# serial-con.net
KiCad netlist of a schematic drawn in Altium Designer
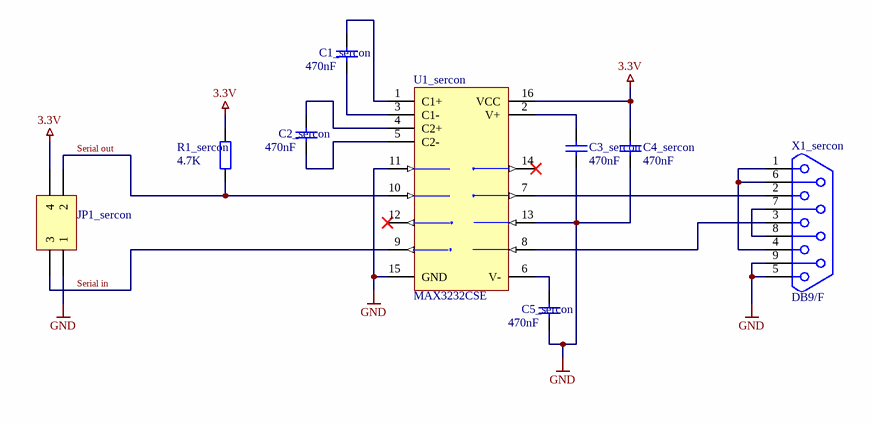
[diagram p0: serial-con.SchDoc]

(export (version "E")
  (design (tool "Eeschema 10.0.6"))
  (components
    (comp (ref "1_sercon")
      (value "CC License")
      (footprint "CC-License")
      (libsource (lib "gecko3-user") (part "CC License"))
    )
    (comp (ref "C1_sercon")
      (value "470nF")
      (footprint "0603")
      (description "Capacitor")
      (fields
        (field (name "MANUFACTURER") "PHYCOMP")
        (field (name "PART NUMBER") "2238 786 19758")
        (field (name "PUBLISHER") "Altium Limited")
      )
      (libsource (lib "Miscellaneous Devices") (part "Cap"))
    )
    (comp (ref "C2_sercon")
      (value "470nF")
      (footprint "0603")
      (description "Capacitor")
      (fields
        (field (name "MANUFACTURER") "PHYCOMP")
        (field (name "PART NUMBER") "2238 786 19758")
        (field (name "PUBLISHER") "Altium Limited")
      )
      (libsource (lib "Miscellaneous Devices") (part "Cap"))
    )
    (comp (ref "C3_sercon")
      (value "470nF")
      (footprint "0603")
      (description "Capacitor")
      (fields
        (field (name "MANUFACTURER") "PHYCOMP")
        (field (name "PART NUMBER") "2238 786 19758")
        (field (name "PUBLISHER") "Altium Limited")
      )
      (libsource (lib "Miscellaneous Devices") (part "Cap"))
    )
    (comp (ref "C4_sercon")
      (value "470nF")
      (footprint "0603")
      (description "Capacitor")
      (fields
        (field (name "MANUFACTURER") "PHYCOMP")
        (field (name "PART NUMBER") "2238 786 19758")
        (field (name "PUBLISHER") "Altium Limited")
      )
      (libsource (lib "Miscellaneous Devices") (part "Cap"))
    )
    (comp (ref "C5_sercon")
      (value "470nF")
      (footprint "0603")
      (description "Capacitor")
      (fields
        (field (name "MANUFACTURER") "PHYCOMP")
        (field (name "PART NUMBER") "2238 786 19758")
        (field (name "PUBLISHER") "Altium Limited")
      )
      (libsource (lib "Miscellaneous Devices") (part "Cap"))
    )
    (comp (ref "JP1_sercon")
      (value "M22-2040205")
      (footprint "M22-2040205")
      (fields (field (name "MANUFACTURER") "HARWIN"))
      (libsource (lib "gecko3-user") (part "M22-2040205"))
    )
    (comp (ref "R1_sercon")
      (value "4.7K")
      (footprint "0402")
      (description "Resistor")
      (fields
        (field (name "MANUFACTURER") "PHYCOMP")
        (field (name "PART NUMBER") "232270674702")
        (field (name "PUBLISHER") "Altium Limited")
      )
      (libsource (lib "Miscellaneous Devices") (part "Res2"))
    )
    (comp (ref "U1_sercon")
      (value "MAX3232CSE")
      (footprint "SO-G16")
      (description "3.0V TO 5.5V, Low-Power, up to 1Mbps, True RS-232 Transceiver Using Four 0.1µF External Capacitor")
      (fields
        (field (name "MANUFACTURER") "Maxim")
        (field (name "PART NUMBER") "MAX 3232 CSE")
        (field (name "PUBLISHER") "Altium Limited")
      )
      (libsource (lib "Maxim Communication Transceiver") (part "MAX3232CSE"))
    )
    (comp (ref "X1_sercon")
      (value "DB9/F")
      (footprint "DSUB9RA/F")
      (fields (field (name "MANUFACTURER") "MULTICOMP") (field (name "PART NUMBER") "5504F1-09S-01-03-F1"))
      (libsource (lib "gecko3-user") (part "DB9/F"))
    )
  )
  (nets
    (net (code "1") (name "/Serial in") (class "Default")
      (node (ref "JP1_sercon") (pin "3") (pinfunction "3_3") (pintype "passive"))
      (node (ref "U1_sercon") (pin "9") (pinfunction "R2OUT_9") (pintype "output"))
    )
    (net (code "2") (name "/Serial out") (class "Default")
      (node (ref "JP1_sercon") (pin "2") (pinfunction "2_2") (pintype "passive"))
      (node (ref "R1_sercon") (pin "1") (pinfunction "1_1") (pintype "passive"))
      (node (ref "U1_sercon") (pin "10") (pinfunction "T2IN_10") (pintype "input"))
    )
    (net (code "3") (name "3.3V") (class "Default")
      (node (ref "C4_sercon") (pin "2") (pinfunction "2_2") (pintype "passive"))
      (node (ref "JP1_sercon") (pin "4") (pinfunction "4_4") (pintype "passive"))
      (node (ref "R1_sercon") (pin "2") (pinfunction "2_2") (pintype "passive"))
      (node (ref "U1_sercon") (pin "16") (pinfunction "VCC_16") (pintype "power_in"))
    )
    (net (code "4") (name "GND") (class "Default")
      (node (ref "C3_sercon") (pin "1") (pinfunction "1_1") (pintype "passive"))
      (node (ref "C4_sercon") (pin "1") (pinfunction "1_1") (pintype "passive"))
      (node (ref "C5_sercon") (pin "1") (pinfunction "1_1") (pintype "passive"))
      (node (ref "JP1_sercon") (pin "1") (pinfunction "1_1") (pintype "passive"))
      (node (ref "U1_sercon") (pin "11") (pinfunction "T1IN_11") (pintype "input"))
      (node (ref "U1_sercon") (pin "13") (pinfunction "R1IN_13") (pintype "input"))
      (node (ref "U1_sercon") (pin "15") (pinfunction "GND_15") (pintype "power_in"))
      (node (ref "X1_sercon") (pin "5") (pinfunction "5_5") (pintype "passive"))
      (node (ref "X1_sercon") (pin "9") (pinfunction "9_9") (pintype "passive"))
    )
    (net (code "5") (name "Net-(U1_sercon-C1+)") (class "Default")
      (node (ref "C1_sercon") (pin "2") (pinfunction "2_2") (pintype "passive"))
      (node (ref "U1_sercon") (pin "1") (pinfunction "C1+_1") (pintype "passive"))
    )
    (net (code "6") (name "Net-(U1_sercon-C1-)") (class "Default")
      (node (ref "C1_sercon") (pin "1") (pinfunction "1_1") (pintype "passive"))
      (node (ref "U1_sercon") (pin "3") (pinfunction "C1-_3") (pintype "passive"))
    )
    (net (code "7") (name "Net-(U1_sercon-C2+)") (class "Default")
      (node (ref "C2_sercon") (pin "2") (pinfunction "2_2") (pintype "passive"))
      (node (ref "U1_sercon") (pin "4") (pinfunction "C2+_4") (pintype "passive"))
    )
    (net (code "8") (name "Net-(U1_sercon-C2-)") (class "Default")
      (node (ref "C2_sercon") (pin "1") (pinfunction "1_1") (pintype "passive"))
      (node (ref "U1_sercon") (pin "5") (pinfunction "C2-_5") (pintype "passive"))
    )
    (net (code "9") (name "Net-(U1_sercon-R2IN)") (class "Default")
      (node (ref "U1_sercon") (pin "8") (pinfunction "R2IN_8") (pintype "input"))
      (node (ref "X1_sercon") (pin "3") (pinfunction "3_3") (pintype "passive"))
    )
    (net (code "10") (name "Net-(U1_sercon-T2OUT)") (class "Default")
      (node (ref "U1_sercon") (pin "7") (pinfunction "T2OUT_7") (pintype "output"))
      (node (ref "X1_sercon") (pin "2") (pinfunction "2_2") (pintype "passive"))
    )
    (net (code "11") (name "Net-(U1_sercon-V+)") (class "Default")
      (node (ref "C3_sercon") (pin "2") (pinfunction "2_2") (pintype "passive"))
      (node (ref "U1_sercon") (pin "2") (pinfunction "V+_2") (pintype "power_in"))
    )
    (net (code "12") (name "Net-(U1_sercon-V-)") (class "Default")
      (node (ref "C5_sercon") (pin "2") (pinfunction "2_2") (pintype "passive"))
      (node (ref "U1_sercon") (pin "6") (pinfunction "V-_6") (pintype "power_in"))
    )
    (net (code "13") (name "Net-(X1_sercon-Pad1)") (class "Default")
      (node (ref "X1_sercon") (pin "1") (pinfunction "1_1") (pintype "passive"))
      (node (ref "X1_sercon") (pin "4") (pinfunction "4_4") (pintype "passive"))
      (node (ref "X1_sercon") (pin "6") (pinfunction "6_6") (pintype "passive"))
    )
    (net (code "14") (name "Net-(X1_sercon-Pad7)") (class "Default")
      (node (ref "X1_sercon") (pin "7") (pinfunction "7_7") (pintype "passive"))
      (node (ref "X1_sercon") (pin "8") (pinfunction "8_8") (pintype "passive"))
    )
    (net (code "15") (name "unconnected-(U1_sercon-R1OUT-Pad12)") (class "Default")
      (node (ref "U1_sercon") (pin "12") (pinfunction "R1OUT_12") (pintype "output+no_connect"))
    )
    (net (code "16") (name "unconnected-(U1_sercon-T1OUT-Pad14)") (class "Default")
      (node (ref "U1_sercon") (pin "14") (pinfunction "T1OUT_14") (pintype "output+no_connect"))
    )
  )
)
